# 07_USB.net
KiCad netlist of a schematic drawn in Altium Designer
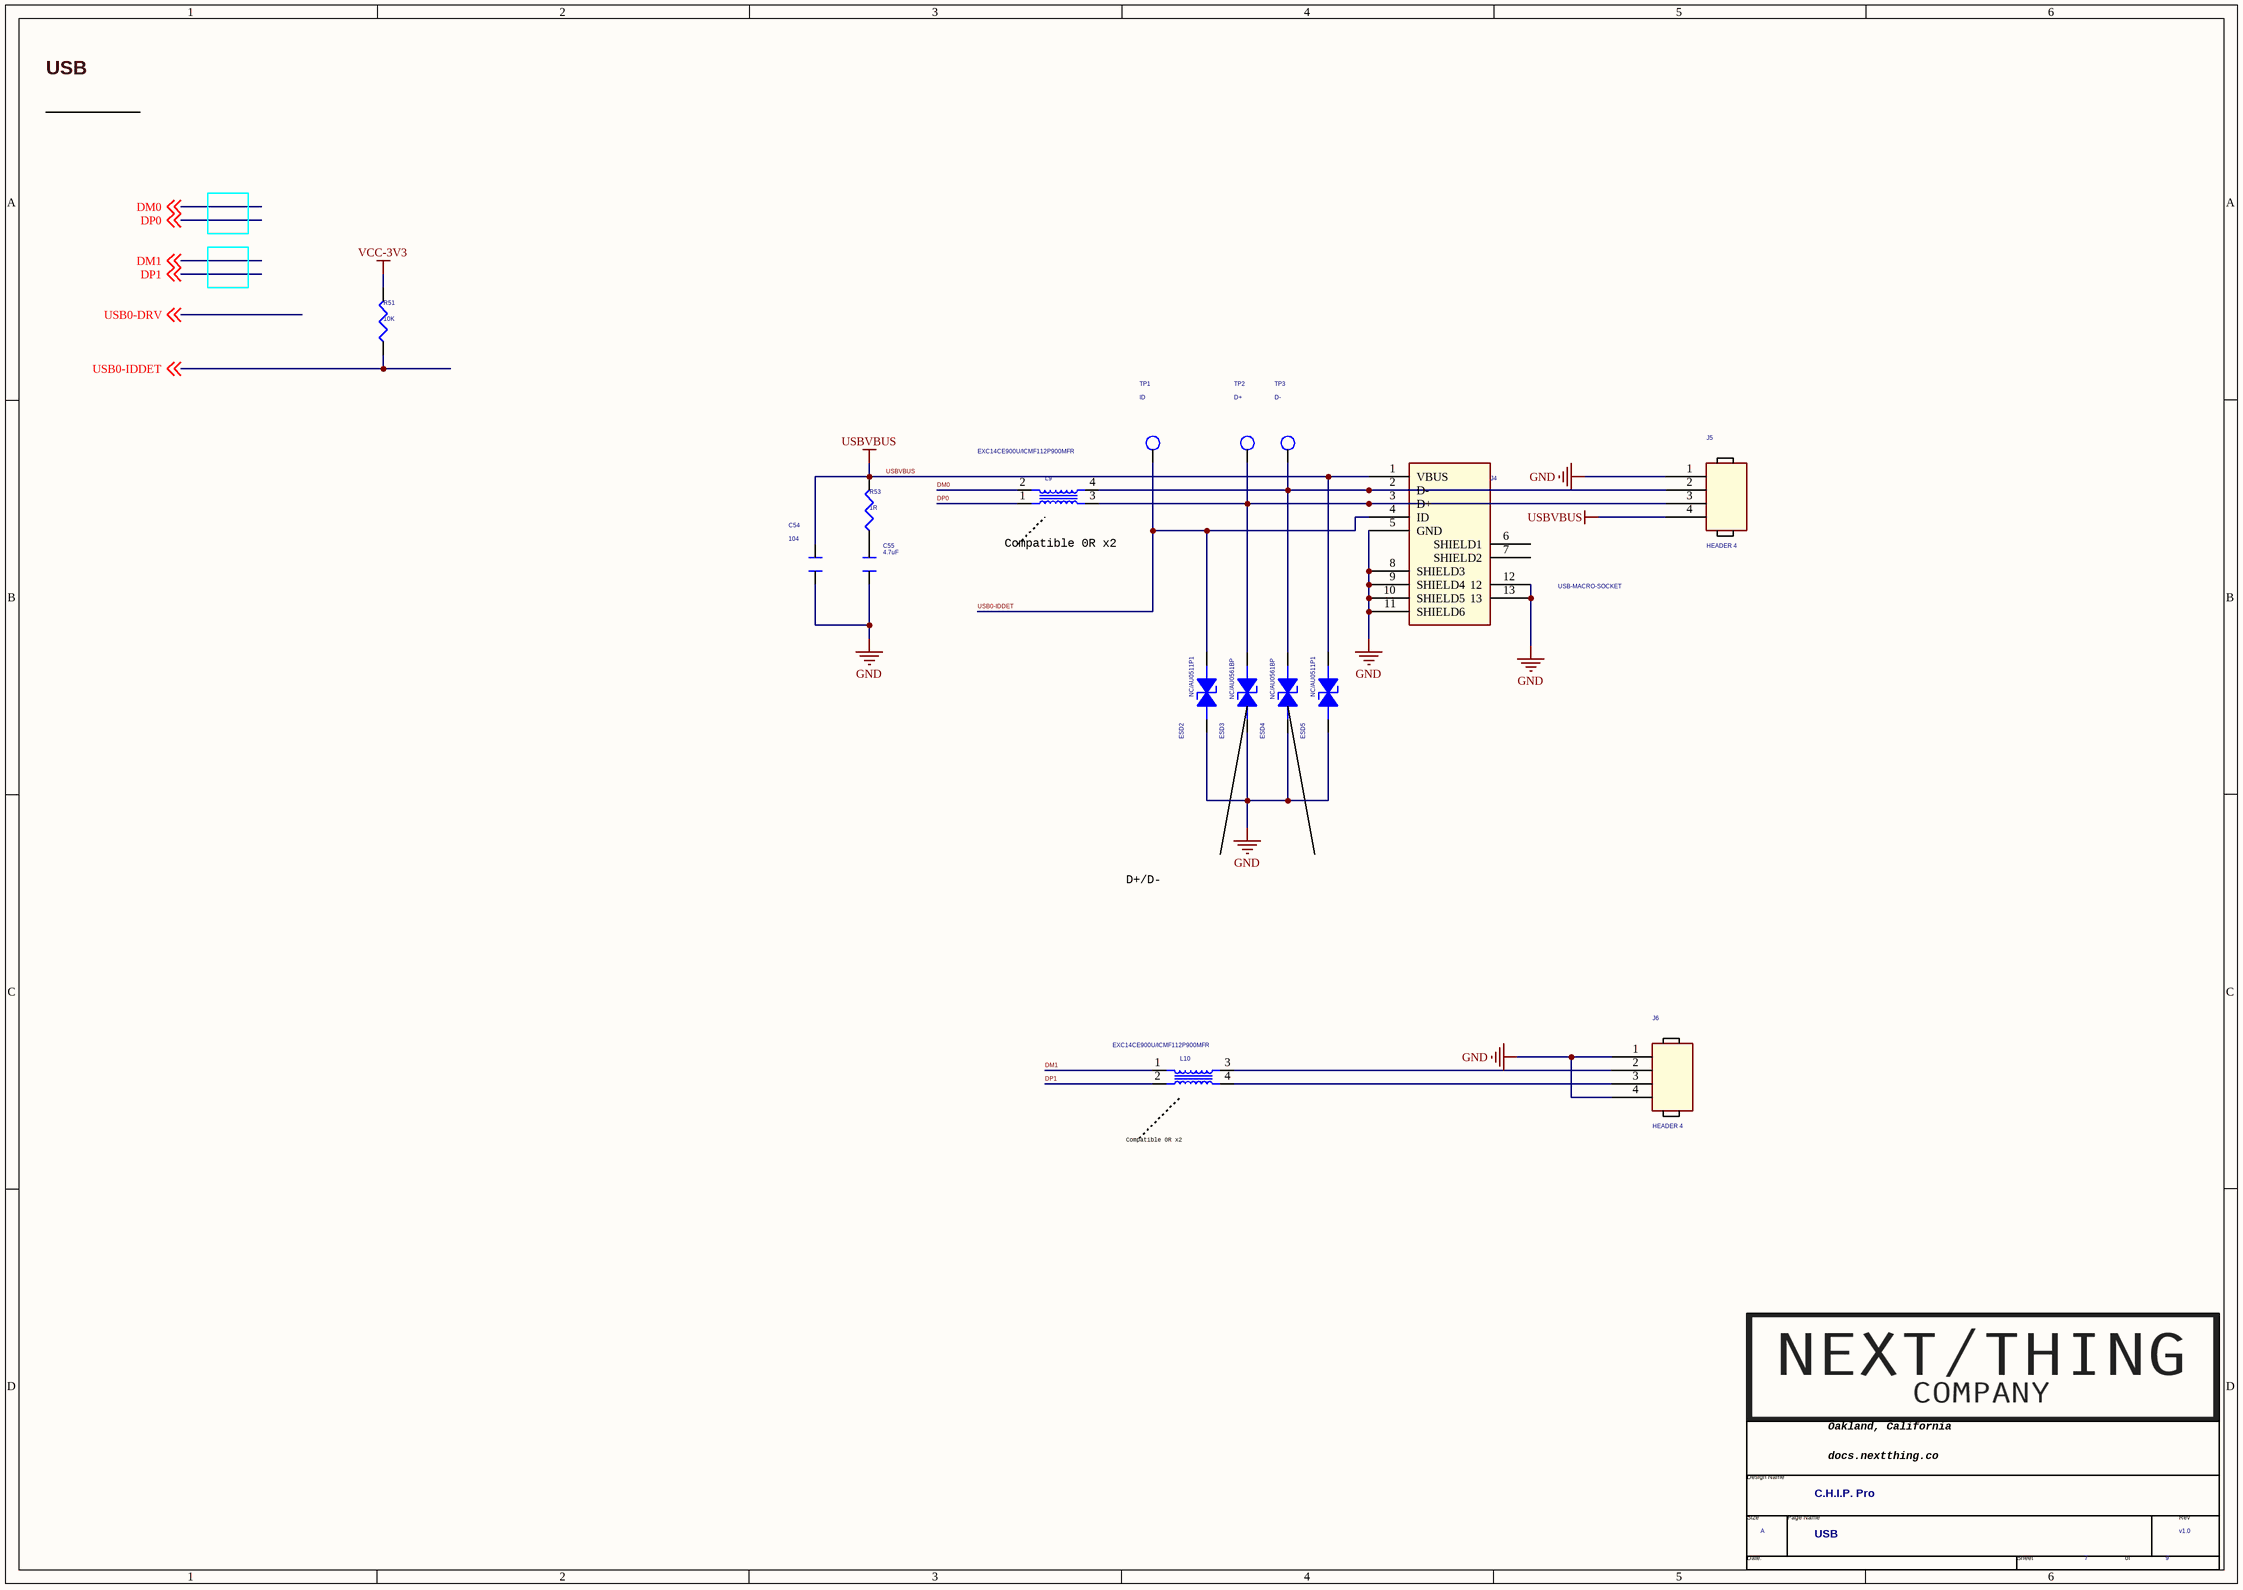
[diagram p0: 07 USB.SchDoc]

(export (version "E")
  (design (tool "Eeschema 10.0.6"))
  (components
    (comp (ref "C54") (value "104") (footprint "C0201") (libsource (lib "*") (part "CAPACITOR")))
    (comp (ref "C55") (value "4.7uF") (footprint "C0603") (libsource (lib "*") (part "CAPACITOR")))
    (comp (ref "ESD2") (value "NC/AU0511P1") (footprint "ESD0402") (libsource (lib "*") (part "1_1.5KE100A")))
    (comp (ref "ESD3") (value "NC/AU0561BP") (footprint "ESD0402") (libsource (lib "*") (part "1_1.5KE100A")))
    (comp (ref "ESD4") (value "NC/AU0561BP") (footprint "ESD0402") (libsource (lib "*") (part "1_1.5KE100A")))
    (comp (ref "ESD5") (value "NC/AU0511P1") (footprint "ESD0402") (libsource (lib "*") (part "1_1.5KE100A")))
    (comp (ref "J4")
      (value "USB-MACRO-SOCKET")
      (footprint "USB_MINI_AB")
      (libsource (lib "*") (part "USB_MINI_SOCKET_2"))
    )
    (comp (ref "J5") (value "HEADER 4") (footprint "stampvia4") (libsource (lib "*") (part "HEADER 4")))
    (comp (ref "J6") (value "HEADER 4") (footprint "stampvia4") (libsource (lib "*") (part "HEADER 4")))
    (comp (ref "L9")
      (value "EXC14CE900U/ICMF112P900MFR")
      (footprint "L0805x2")
      (libsource (lib "") (part "R-PACK4_0_1"))
    )
    (comp (ref "L10")
      (value "EXC14CE900U/ICMF112P900MFR")
      (footprint "L0805x2")
      (libsource (lib "*") (part "R-PACK4_0"))
    )
    (comp (ref "R51") (value "10K") (footprint "R0201") (libsource (lib "*") (part "R_Dup2")))
    (comp (ref "R53") (value "1R") (footprint "R0402") (libsource (lib "*") (part "R_Dup2")))
    (comp (ref "TP1") (value "ID") (footprint "tp40_smd") (libsource (lib "*") (part "T_POINT_R")))
    (comp (ref "TP2") (value "D+") (footprint "tp40_smd") (libsource (lib "*") (part "T_POINT_R")))
    (comp (ref "TP3") (value "D-") (footprint "tp40_smd") (libsource (lib "*") (part "T_POINT_R")))
  )
  (nets
    (net (code "1") (name "DM0") (class "Default")
      (node (ref "L9") (pin "2") (pinfunction "R2_2") (pintype "passive"))
    )
    (net (code "2") (name "DM1") (class "Default")
      (node (ref "L10") (pin "1") (pinfunction "R1_1") (pintype "passive"))
    )
    (net (code "3") (name "DP0") (class "Default")
      (node (ref "L9") (pin "1") (pinfunction "R1_1") (pintype "passive"))
    )
    (net (code "4") (name "DP1") (class "Default")
      (node (ref "L10") (pin "2") (pinfunction "R2_2") (pintype "passive"))
    )
    (net (code "5") (name "GND") (class "Default")
      (node (ref "C54") (pin "1") (pinfunction "1_1") (pintype "passive"))
      (node (ref "C55") (pin "1") (pinfunction "1_1") (pintype "passive"))
      (node (ref "ESD2") (pin "2") (pinfunction "CATHODE_2") (pintype "passive"))
      (node (ref "ESD3") (pin "2") (pinfunction "CATHODE_2") (pintype "passive"))
      (node (ref "ESD4") (pin "2") (pinfunction "CATHODE_2") (pintype "passive"))
      (node (ref "ESD5") (pin "2") (pinfunction "CATHODE_2") (pintype "passive"))
      (node (ref "J4") (pin "10") (pinfunction "SHIELD5_10") (pintype "passive"))
      (node (ref "J4") (pin "11") (pinfunction "SHIELD6_11") (pintype "passive"))
      (node (ref "J4") (pin "12") (pinfunction "12_12") (pintype "passive"))
      (node (ref "J4") (pin "13") (pinfunction "13_13") (pintype "passive"))
      (node (ref "J4") (pin "5") (pinfunction "GND_5") (pintype "passive"))
      (node (ref "J4") (pin "8") (pinfunction "SHIELD3_8") (pintype "passive"))
      (node (ref "J4") (pin "9") (pinfunction "SHIELD4_9") (pintype "passive"))
      (node (ref "J5") (pin "1") (pinfunction "1_1") (pintype "passive"))
      (node (ref "J6") (pin "1") (pinfunction "1_1") (pintype "passive"))
      (node (ref "J6") (pin "4") (pinfunction "4_4") (pintype "passive"))
    )
    (net (code "6") (name "Net-(C55-Pad2)") (class "Default")
      (node (ref "C55") (pin "2") (pinfunction "2_2") (pintype "passive"))
      (node (ref "R53") (pin "1") (pinfunction "1_1") (pintype "passive"))
    )
    (net (code "7") (name "Net-(ESD3-ANODE)") (class "Default")
      (node (ref "ESD3") (pin "1") (pinfunction "ANODE_1") (pintype "passive"))
      (node (ref "J4") (pin "3") (pinfunction "D+_3") (pintype "passive"))
      (node (ref "J5") (pin "3") (pinfunction "3_3") (pintype "passive"))
      (node (ref "L9") (pin "3") (pinfunction "R3_3") (pintype "passive"))
      (node (ref "TP2") (pin "1") (pinfunction "TP_1") (pintype "passive"))
    )
    (net (code "8") (name "Net-(ESD4-ANODE)") (class "Default")
      (node (ref "ESD4") (pin "1") (pinfunction "ANODE_1") (pintype "passive"))
      (node (ref "J4") (pin "2") (pinfunction "D-_2") (pintype "passive"))
      (node (ref "J5") (pin "2") (pinfunction "2_2") (pintype "passive"))
      (node (ref "L9") (pin "4") (pinfunction "R4_4") (pintype "passive"))
      (node (ref "TP3") (pin "1") (pinfunction "TP_1") (pintype "passive"))
    )
    (net (code "9") (name "Net-(L10-R3)") (class "Default")
      (node (ref "J6") (pin "2") (pinfunction "2_2") (pintype "passive"))
      (node (ref "L10") (pin "3") (pinfunction "R3_3") (pintype "passive"))
    )
    (net (code "10") (name "Net-(L10-R4)") (class "Default")
      (node (ref "J6") (pin "3") (pinfunction "3_3") (pintype "passive"))
      (node (ref "L10") (pin "4") (pinfunction "R4_4") (pintype "passive"))
    )
    (net (code "12") (name "USB0-IDDET") (class "Default")
      (node (ref "ESD2") (pin "1") (pinfunction "ANODE_1") (pintype "passive"))
      (node (ref "J4") (pin "4") (pinfunction "ID_4") (pintype "passive"))
      (node (ref "R51") (pin "1") (pinfunction "1_1") (pintype "passive"))
      (node (ref "TP1") (pin "1") (pinfunction "TP_1") (pintype "passive"))
    )
    (net (code "13") (name "USBVBUS") (class "Default")
      (node (ref "C54") (pin "2") (pinfunction "2_2") (pintype "passive"))
      (node (ref "ESD5") (pin "1") (pinfunction "ANODE_1") (pintype "passive"))
      (node (ref "J4") (pin "1") (pinfunction "VBUS_1") (pintype "passive"))
      (node (ref "J5") (pin "4") (pinfunction "4_4") (pintype "passive"))
      (node (ref "R53") (pin "2") (pinfunction "2_2") (pintype "passive"))
    )
    (net (code "14") (name "VCC-3V3") (class "Default")
      (node (ref "R51") (pin "2") (pinfunction "2_2") (pintype "passive"))
    )
    (net (code "15") (name "unconnected-(J4-SHIELD1-Pad6)") (class "Default")
      (node (ref "J4") (pin "6") (pinfunction "SHIELD1_6") (pintype "passive"))
    )
    (net (code "16") (name "unconnected-(J4-SHIELD2-Pad7)") (class "Default")
      (node (ref "J4") (pin "7") (pinfunction "SHIELD2_7") (pintype "passive"))
    )
  )
)
